# 02-Mezzanine.net
KiCad netlist of a schematic drawn in Altium Designer
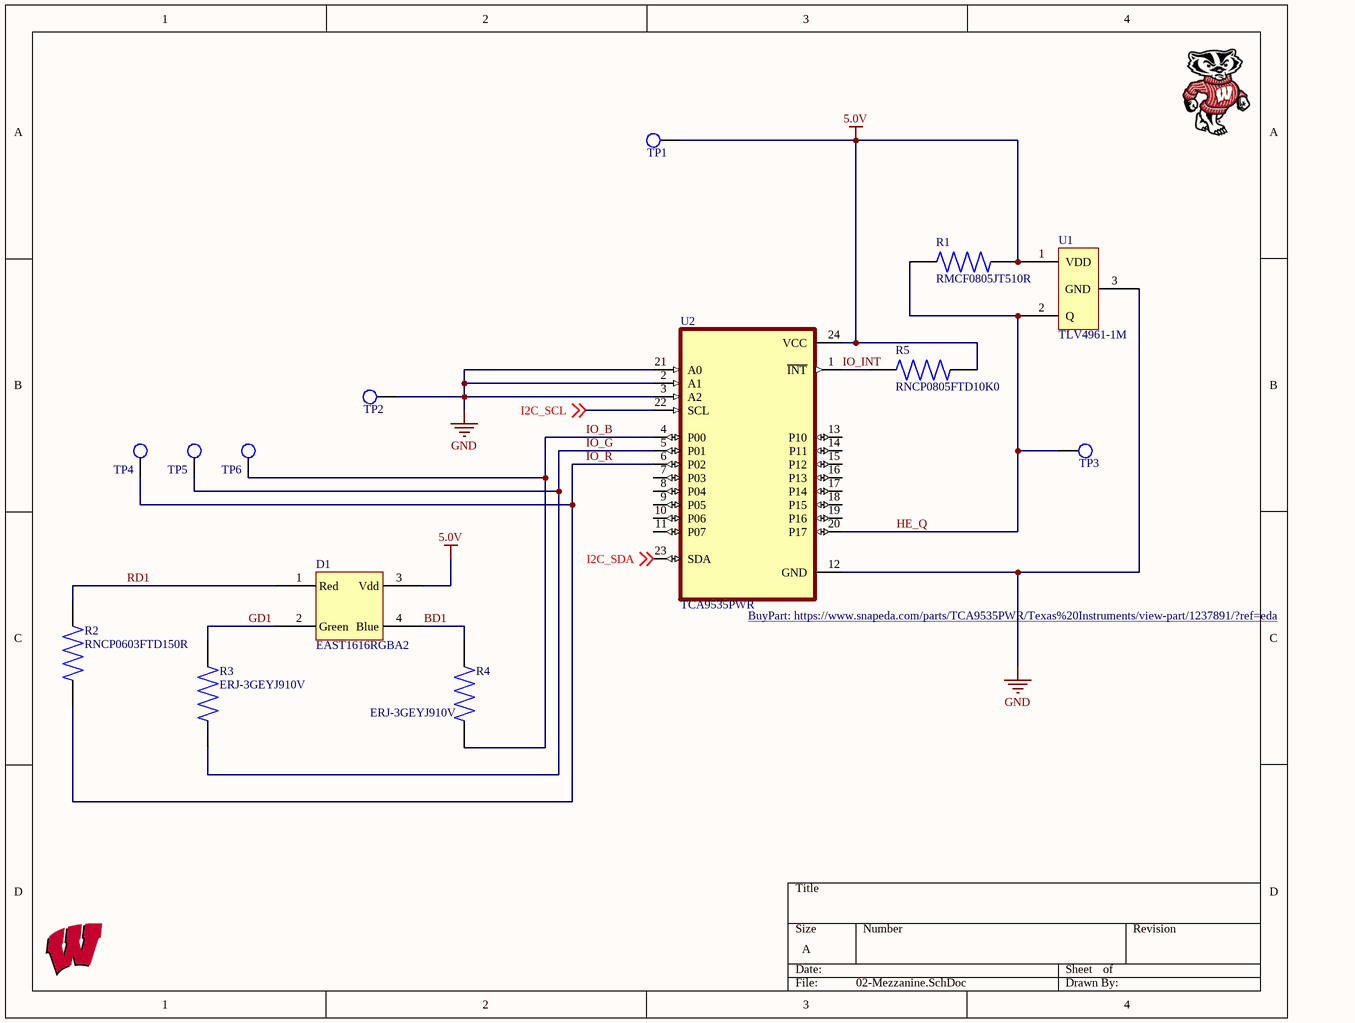
[diagram p0: 02-Mezzanine.SchDoc]

(export (version "E")
  (design (tool "Eeschema 10.0.6"))
  (components
    (comp (ref "D1")
      (value "EAST1616RGBA2")
      (footprint "EAST1616RGBA2")
      (libsource (lib "chess_module") (part "EAST1616RGBA2"))
    )
    (comp (ref "R1")
      (value "RMCF0805JT510R")
      (footprint "RESC2012X65N")
      (libsource (lib "chess_module") (part "RMCF0805JT510R"))
    )
    (comp (ref "R2")
      (value "RNCP0603FTD150R")
      (footprint "RESC1508X50N")
      (libsource (lib "chess_module") (part "RNCP0603FTD150R"))
    )
    (comp (ref "R3")
      (value "ERJ-3GEYJ910V")
      (footprint "RESC1608X55N")
      (description "Res Thick Film 0603 91 Ohm 5% 1/10W Ã‚Â±200ppm/Ã‚Â°C Molded SMD SMD Punched Carrier T/R")
      (libsource (lib "chess_module") (part "ERJ-3GEYJ910V"))
    )
    (comp (ref "R4")
      (value "ERJ-3GEYJ910V")
      (footprint "RESC1608X55N")
      (description "Res Thick Film 0603 91 Ohm 5% 1/10W Ã‚Â±200ppm/Ã‚Â°C Molded SMD SMD Punched Carrier T/R")
      (libsource (lib "chess_module") (part "ERJ-3GEYJ910V"))
    )
    (comp (ref "R5")
      (value "RNCP0805FTD10K0")
      (footprint "RESC2012X60N")
      (fields
        (field (name "DIGI-KEY_PART_NUMBER") "RNCP0805FTD10K0CT-ND")
        (field (name "MF") "Stackpole Electronics Inc")
      )
      (libsource (lib "chess_module") (part "RNCP0805FTD10K0"))
    )
    (comp (ref "TP1")
      (value "TP_1206")
      (footprint "TP-SMC-1206")
      (description "Test Point SMD 1206")
      (fields
        (field (name "MANUFACTURER") "TE Connectivity (Tyco Electronics)")
        (field (name "MANUFACTURER PART NUMBER") "1625854-1")
      )
      (libsource (lib "ECE453-F22-Power") (part "TP_1206"))
    )
    (comp (ref "TP2")
      (value "TP_1206")
      (footprint "TP-SMC-1206")
      (description "Test Point SMD 1206")
      (fields
        (field (name "MANUFACTURER") "TE Connectivity (Tyco Electronics)")
        (field (name "MANUFACTURER PART NUMBER") "1625854-1")
      )
      (libsource (lib "ECE453-F22-Power") (part "TP_1206"))
    )
    (comp (ref "TP3")
      (value "TP_1206")
      (footprint "TP-SMC-1206")
      (description "Test Point SMD 1206")
      (fields
        (field (name "MANUFACTURER") "TE Connectivity (Tyco Electronics)")
        (field (name "MANUFACTURER PART NUMBER") "1625854-1")
      )
      (libsource (lib "ECE453-F22-Power") (part "TP_1206"))
    )
    (comp (ref "TP4")
      (value "TP_1206")
      (footprint "TP-SMC-1206")
      (description "Test Point SMD 1206")
      (fields
        (field (name "MANUFACTURER") "TE Connectivity (Tyco Electronics)")
        (field (name "MANUFACTURER PART NUMBER") "1625854-1")
      )
      (libsource (lib "ECE453-F22-Power") (part "TP_1206"))
    )
    (comp (ref "TP5")
      (value "TP_1206")
      (footprint "TP-SMC-1206")
      (description "Test Point SMD 1206")
      (fields
        (field (name "MANUFACTURER") "TE Connectivity (Tyco Electronics)")
        (field (name "MANUFACTURER PART NUMBER") "1625854-1")
      )
      (libsource (lib "ECE453-F22-Power") (part "TP_1206"))
    )
    (comp (ref "TP6")
      (value "TP_1206")
      (footprint "TP-SMC-1206")
      (description "Test Point SMD 1206")
      (fields
        (field (name "MANUFACTURER") "TE Connectivity (Tyco Electronics)")
        (field (name "MANUFACTURER PART NUMBER") "1625854-1")
      )
      (libsource (lib "ECE453-F22-Power") (part "TP_1206"))
    )
    (comp (ref "U1")
      (value "TLV4961-1M")
      (footprint "SOT95P245X110-3N")
      (description "Hall Effect Sensor")
      (libsource (lib "chess_module") (part "TLV4961-1M"))
    )
    (comp (ref "U2")
      (value "TCA9535PWR")
      (footprint "SOP65P640X120-24N")
      (fields
        (field (name "MF") "Texas Instruments")
        (field (name "BUYPART") "https://www.snapeda.com/parts/TCA9535PWR/Texas%20Instruments/view-part/1237891/?ref=eda")
      )
      (libsource (lib "chess_module") (part "TCA9535PWR"))
    )
  )
  (nets
    (net (code "1") (name "/BD1") (class "Default")
      (node (ref "D1") (pin "4") (pinfunction "Blue_4") (pintype "passive"))
      (node (ref "R4") (pin "2") (pinfunction "2_2") (pintype "passive"))
    )
    (net (code "2") (name "/GD1") (class "Default")
      (node (ref "D1") (pin "2") (pinfunction "Green_2") (pintype "passive"))
      (node (ref "R3") (pin "2") (pinfunction "2_2") (pintype "passive"))
    )
    (net (code "3") (name "/HE_Q") (class "Default")
      (node (ref "R1") (pin "1") (pinfunction "1_1") (pintype "passive"))
      (node (ref "TP3") (pin "1") (pintype "passive"))
      (node (ref "U1") (pin "2") (pinfunction "Q_2") (pintype "passive"))
      (node (ref "U2") (pin "20") (pinfunction "P17_20") (pintype "bidirectional"))
    )
    (net (code "4") (name "/IO_B") (class "Default")
      (node (ref "R4") (pin "1") (pinfunction "1_1") (pintype "passive"))
      (node (ref "TP6") (pin "1") (pintype "passive"))
      (node (ref "U2") (pin "4") (pinfunction "P00_4") (pintype "bidirectional"))
    )
    (net (code "5") (name "/IO_G") (class "Default")
      (node (ref "R3") (pin "1") (pinfunction "1_1") (pintype "passive"))
      (node (ref "TP5") (pin "1") (pintype "passive"))
      (node (ref "U2") (pin "5") (pinfunction "P01_5") (pintype "bidirectional"))
    )
    (net (code "6") (name "/IO_INT") (class "Default")
      (node (ref "R5") (pin "1") (pinfunction "1_1") (pintype "passive"))
      (node (ref "U2") (pin "1") (pinfunction "~{INT}_1") (pintype "output"))
    )
    (net (code "7") (name "/IO_R") (class "Default")
      (node (ref "R2") (pin "1") (pinfunction "1_1") (pintype "passive"))
      (node (ref "TP4") (pin "1") (pintype "passive"))
      (node (ref "U2") (pin "6") (pinfunction "P02_6") (pintype "bidirectional"))
    )
    (net (code "8") (name "/RD1") (class "Default")
      (node (ref "D1") (pin "1") (pinfunction "Red_1") (pintype "passive"))
      (node (ref "R2") (pin "2") (pinfunction "2_2") (pintype "passive"))
    )
    (net (code "9") (name "5.0V") (class "Default")
      (node (ref "D1") (pin "3") (pinfunction "Vdd_3") (pintype "passive"))
      (node (ref "R1") (pin "2") (pinfunction "2_2") (pintype "passive"))
      (node (ref "R5") (pin "2") (pinfunction "2_2") (pintype "passive"))
      (node (ref "TP1") (pin "1") (pintype "passive"))
      (node (ref "U1") (pin "1") (pinfunction "VDD_1") (pintype "passive"))
      (node (ref "U2") (pin "24") (pinfunction "VCC_24") (pintype "power_in"))
    )
    (net (code "10") (name "GND") (class "Default")
      (node (ref "TP2") (pin "1") (pintype "passive"))
      (node (ref "U1") (pin "3") (pinfunction "GND_3") (pintype "passive"))
      (node (ref "U2") (pin "12") (pinfunction "GND_12") (pintype "power_in"))
      (node (ref "U2") (pin "2") (pinfunction "A1_2") (pintype "input"))
      (node (ref "U2") (pin "21") (pinfunction "A0_21") (pintype "input"))
      (node (ref "U2") (pin "3") (pinfunction "A2_3") (pintype "input"))
    )
    (net (code "11") (name "I2C_SCL") (class "Default")
      (node (ref "U2") (pin "22") (pinfunction "SCL_22") (pintype "input"))
    )
    (net (code "12") (name "I2C_SDA") (class "Default")
      (node (ref "U2") (pin "23") (pinfunction "SDA_23") (pintype "bidirectional"))
    )
    (net (code "13") (name "unconnected-(U2-P03-Pad7)") (class "Default")
      (node (ref "U2") (pin "7") (pinfunction "P03_7") (pintype "bidirectional"))
    )
    (net (code "14") (name "unconnected-(U2-P04-Pad8)") (class "Default")
      (node (ref "U2") (pin "8") (pinfunction "P04_8") (pintype "bidirectional"))
    )
    (net (code "15") (name "unconnected-(U2-P05-Pad9)") (class "Default")
      (node (ref "U2") (pin "9") (pinfunction "P05_9") (pintype "bidirectional"))
    )
    (net (code "16") (name "unconnected-(U2-P06-Pad10)") (class "Default")
      (node (ref "U2") (pin "10") (pinfunction "P06_10") (pintype "bidirectional"))
    )
    (net (code "17") (name "unconnected-(U2-P07-Pad11)") (class "Default")
      (node (ref "U2") (pin "11") (pinfunction "P07_11") (pintype "bidirectional"))
    )
    (net (code "18") (name "unconnected-(U2-P10-Pad13)") (class "Default")
      (node (ref "U2") (pin "13") (pinfunction "P10_13") (pintype "bidirectional"))
    )
    (net (code "19") (name "unconnected-(U2-P11-Pad14)") (class "Default")
      (node (ref "U2") (pin "14") (pinfunction "P11_14") (pintype "bidirectional"))
    )
    (net (code "20") (name "unconnected-(U2-P12-Pad15)") (class "Default")
      (node (ref "U2") (pin "15") (pinfunction "P12_15") (pintype "bidirectional"))
    )
    (net (code "21") (name "unconnected-(U2-P13-Pad16)") (class "Default")
      (node (ref "U2") (pin "16") (pinfunction "P13_16") (pintype "bidirectional"))
    )
    (net (code "22") (name "unconnected-(U2-P14-Pad17)") (class "Default")
      (node (ref "U2") (pin "17") (pinfunction "P14_17") (pintype "bidirectional"))
    )
    (net (code "23") (name "unconnected-(U2-P15-Pad18)") (class "Default")
      (node (ref "U2") (pin "18") (pinfunction "P15_18") (pintype "bidirectional"))
    )
    (net (code "24") (name "unconnected-(U2-P16-Pad19)") (class "Default")
      (node (ref "U2") (pin "19") (pinfunction "P16_19") (pintype "bidirectional"))
    )
  )
)
